# Reset_Signal_Isolation.net
KiCad netlist of a schematic drawn in Altium Designer
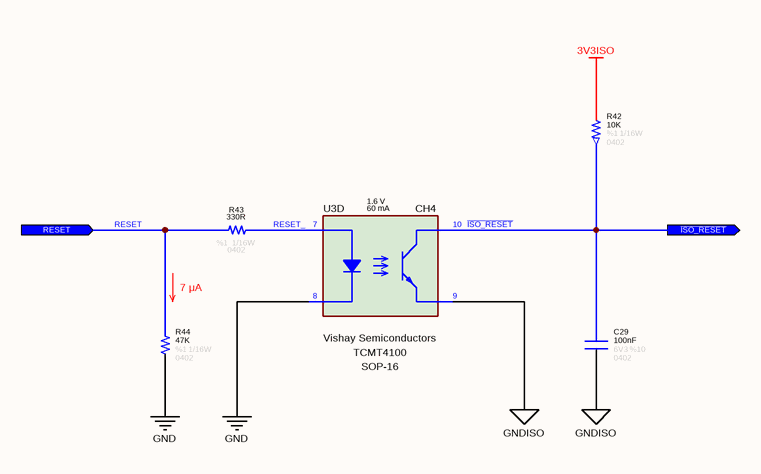
[diagram p0: Reset Signal Isolation.SchDoc]

(export (version "E")
  (design (tool "Eeschema 10.0.6"))
  (components
    (comp (ref "C29")
      (value "100nF")
      (footprint "CAPACITOR_0402")
      (description "Capacitor - 100nF [0402-6V3] (Ceramic)")
      (fields
        (field (name "MANUFACTURER PART NUMBER") "04026D104KAT4A")
        (field (name "TOLERANCE") "%10")
        (field (name "VOLTAGE") "6V3")
        (field (name "CASE") "0402")
        (field (name "Comment") "Capacitor - 100nF [0402] (Ceramic)")
      )
      (libsource (lib "Akkoyun") (part "Capacitor - 100nF [0402-6V3]"))
    )
    (comp (ref "R42")
      (value "10K")
      (footprint "RESISTOR_0402")
      (description "Thick Film Resistors - SMD 1/16 W 10 KOhm 1%")
      (fields
        (field (name "MANUFACTURER PART NUMBER") "CRCW040210K0FKED")
        (field (name "TOLERANCE") "%1")
        (field (name "CASE") "0402")
        (field (name "POWER") "1/16W")
        (field (name "Comment") "10K - 0402 - %1 - 1/16W")
      )
      (libsource (lib "Akkoyun") (part "Resistor - 10K [0402]"))
    )
    (comp (ref "R43")
      (value "330R")
      (footprint "RESISTOR_0402")
      (description "Thick Film Resistors - SMD 1/16 W 330 Ohm 1%")
      (fields
        (field (name "MANUFACTURER PART NUMBER") "CRCW0402330RFKED")
        (field (name "CASE") "0402")
        (field (name "TOLERANCE") "%1")
        (field (name "POWER") "1/16W")
        (field (name "Comment") "330R - 0402 - %1 - 1/16W")
      )
      (libsource (lib "Akkoyun") (part "Resistor - 330R [0402]"))
    )
    (comp (ref "R44")
      (value "47K")
      (footprint "RESISTOR_0402")
      (description "Thick Film Resistors - SMD 1/16 W 47 KOhm 1%")
      (fields
        (field (name "MANUFACTURER PART NUMBER") "CRCW040247K0FKED")
        (field (name "TOLERANCE") "%1")
        (field (name "CASE") "0402")
        (field (name "POWER") "1/16W")
        (field (name "Comment") "47K - 0402 - %1 - 1/16W")
      )
      (libsource (lib "Akkoyun") (part "Resistor - 47K [0402]"))
    )
    (comp (ref "U3")
      (value "TCMT4100")
      (footprint "SO-16")
      (description "OptpCoupler 4CH 16 Pin (SOP16)")
      (fields
        (field (name "IF - FORWARD CURRENT") "60 mA")
        (field (name "VF - FORWARD VOLTAGE") "1.6 V")
        (field (name "MANUFACTURER NAME") "Vishay Semiconductors")
        (field (name "MANUFACTURER PART NUMBER") "TCMT4100")
        (field (name "CASE") "SOP-16")
      )
      (libsource (lib "Akkoyun") (part "IC - TCMT4100"))
    )
  )
  (nets
    (net (code "1") (name "/RESET") (class "Default")
      (node (ref "R43") (pin "2") (pinfunction "2_2") (pintype "passive"))
      (node (ref "R44") (pin "2") (pinfunction "2_2") (pintype "passive"))
    )
    (net (code "2") (name "/RESET_") (class "Default")
      (node (ref "R43") (pin "1") (pinfunction "1_1") (pintype "passive"))
      (node (ref "U3") (pin "7") (pinfunction "Anode_CH4_7") (pintype "passive"))
    )
    (net (code "3") (name "/~{ISO_RESET}") (class "Default")
      (node (ref "C29") (pin "2") (pinfunction "2_2") (pintype "passive"))
      (node (ref "R42") (pin "1") (pinfunction "1_1") (pintype "output"))
      (node (ref "U3") (pin "10") (pinfunction "Collector_CH4_10") (pintype "passive"))
    )
    (net (code "4") (name "3V3ISO") (class "Default")
      (node (ref "R42") (pin "2") (pinfunction "2_2") (pintype "passive"))
    )
    (net (code "5") (name "GND") (class "Default")
      (node (ref "R44") (pin "1") (pinfunction "1_1") (pintype "passive"))
      (node (ref "U3") (pin "8") (pinfunction "Cathode_CH4_8") (pintype "passive"))
    )
    (net (code "6") (name "GNDISO") (class "Default")
      (node (ref "C29") (pin "1") (pinfunction "1_1") (pintype "passive"))
      (node (ref "U3") (pin "9") (pinfunction "Emiter_CH4_9") (pintype "passive"))
    )
  )
)
